# Channel.net
KiCad netlist of a schematic drawn in Altium Designer
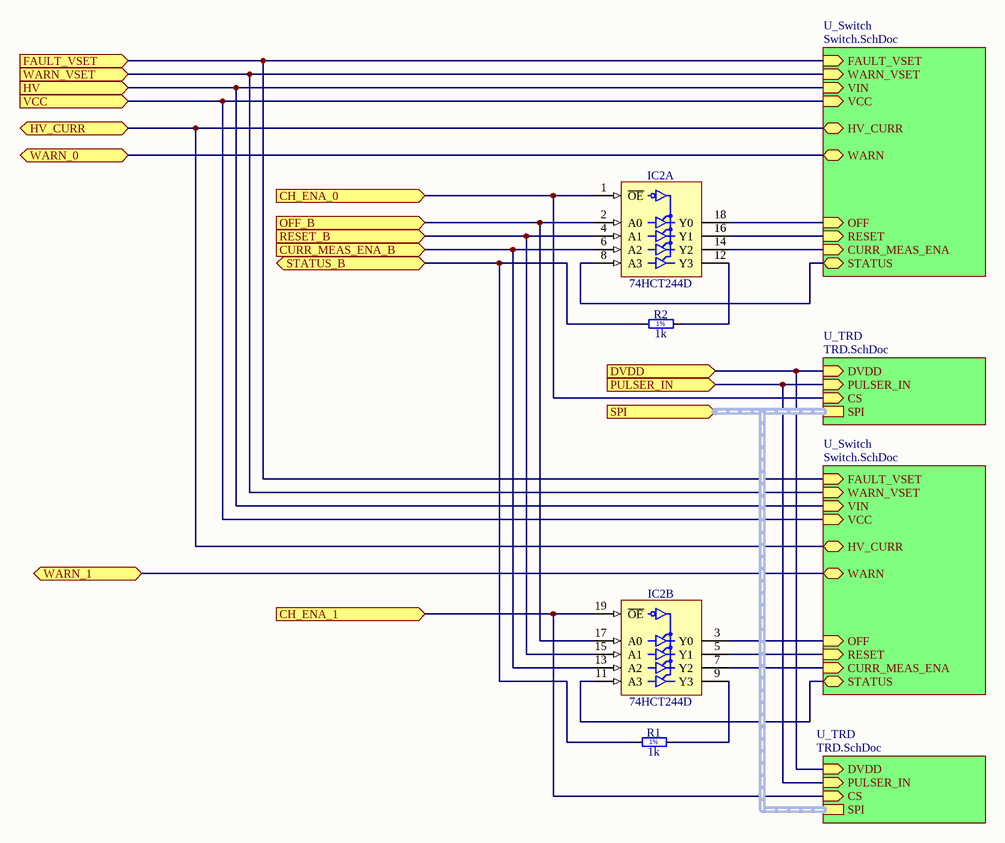
[diagram p0: Channel.SchDoc]

(export (version "E")
  (design (tool "Eeschema 10.0.6"))
  (components
    (comp (ref "IC2")
      (value "74HCT244D")
      (footprint "SOIC127P1032X265-20N")
      (description "Octal Buffer And Line Driver with 3-State Ouputs")
      (fields (field (name "MANUFACTURER") "NXP SEMICONDUCTORS") (field (name "AUTHOR") "CERN DEM JLC"))
      (libsource (lib "ICs And Semiconductors") (part "74244"))
    )
    (comp (ref "R1")
      (value "1k")
      (footprint "RESC2012X60N")
      (description "Resistor - 1%")
      (fields
        (field (name "PART NUMBER") "R0805_1K_1%_0.33W_100PPM_VISHAY_CRCW-HP")
        (field (name "POWER") "0.33W")
        (field (name "AUTHOR") "CERN DEM JLC")
      )
      (libsource (lib "Resistors") (part "Resistor - 1%"))
    )
    (comp (ref "R2")
      (value "1k")
      (footprint "RESC2012X60N")
      (description "Resistor - 1%")
      (fields
        (field (name "PART NUMBER") "R0805_1K_1%_0.33W_100PPM_VISHAY_CRCW-HP")
        (field (name "POWER") "0.33W")
        (field (name "AUTHOR") "CERN DEM JLC")
      )
      (libsource (lib "Resistors") (part "Resistor - 1%"))
    )
  )
  (nets
    (net (code "2") (name "/CH_ENA_0") (class "Default")
      (node (ref "IC2") (pin "1") (pinfunction "~{OE}_1") (pintype "input"))
    )
    (net (code "3") (name "/CH_ENA_1") (class "Default")
      (node (ref "IC2") (pin "19") (pinfunction "~{OE}_19") (pintype "input"))
    )
    (net (code "4") (name "/CURR_MEAS_ENA") (class "Default")
      (node (ref "IC2") (pin "7") (pinfunction "Y2_7") (pintype "tri_state"))
    )
    (net (code "5") (name "/CURR_MEAS_ENA_1") (class "Default")
      (node (ref "IC2") (pin "14") (pinfunction "Y2_14") (pintype "tri_state"))
    )
    (net (code "6") (name "/CURR_MEAS_ENA_B") (class "Default")
      (node (ref "IC2") (pin "13") (pinfunction "A2_13") (pintype "input"))
      (node (ref "IC2") (pin "6") (pinfunction "A2_6") (pintype "input"))
    )
    (net (code "11") (name "/OFF") (class "Default")
      (node (ref "IC2") (pin "3") (pinfunction "Y0_3") (pintype "tri_state"))
    )
    (net (code "12") (name "/OFF_1") (class "Default")
      (node (ref "IC2") (pin "18") (pinfunction "Y0_18") (pintype "tri_state"))
    )
    (net (code "13") (name "/OFF_B") (class "Default")
      (node (ref "IC2") (pin "17") (pinfunction "A0_17") (pintype "input"))
      (node (ref "IC2") (pin "2") (pinfunction "A0_2") (pintype "input"))
    )
    (net (code "15") (name "/RESET") (class "Default")
      (node (ref "IC2") (pin "5") (pinfunction "Y1_5") (pintype "tri_state"))
    )
    (net (code "16") (name "/RESET_1") (class "Default")
      (node (ref "IC2") (pin "16") (pinfunction "Y1_16") (pintype "tri_state"))
    )
    (net (code "17") (name "/RESET_B") (class "Default")
      (node (ref "IC2") (pin "15") (pinfunction "A1_15") (pintype "input"))
      (node (ref "IC2") (pin "4") (pinfunction "A1_4") (pintype "input"))
    )
    (net (code "19") (name "/STATUS") (class "Default")
      (node (ref "IC2") (pin "11") (pinfunction "A3_11") (pintype "input"))
    )
    (net (code "20") (name "/STATUS_1") (class "Default")
      (node (ref "IC2") (pin "8") (pinfunction "A3_8") (pintype "input"))
    )
    (net (code "21") (name "/STATUS_B") (class "Default")
      (node (ref "R1") (pin "1") (pinfunction "1_1") (pintype "passive"))
      (node (ref "R2") (pin "1") (pinfunction "1_1") (pintype "passive"))
    )
    (net (code "25") (name "GND") (class "Default")
      (node (ref "IC2") (pin "10") (pinfunction "GND_10") (pintype "power_in"))
    )
    (net (code "26") (name "Net-(IC2A-Y3)") (class "Default")
      (node (ref "IC2") (pin "12") (pinfunction "Y3_12") (pintype "tri_state"))
      (node (ref "R2") (pin "2") (pinfunction "2_2") (pintype "passive"))
    )
    (net (code "27") (name "Net-(IC2B-Y3)") (class "Default")
      (node (ref "IC2") (pin "9") (pinfunction "Y3_9") (pintype "tri_state"))
      (node (ref "R1") (pin "2") (pinfunction "2_2") (pintype "passive"))
    )
    (net (code "28") (name "VCC") (class "Default")
      (node (ref "IC2") (pin "20") (pinfunction "VCC_20") (pintype "power_in"))
    )
  )
)
